# RAA214023GNP_HCA.net
KiCad netlist of a schematic drawn in Altium Designer
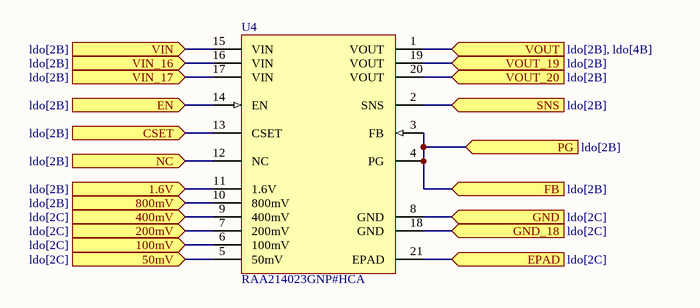
[diagram p0: RAA214023GNP#HCA.SchDoc]

(export (version "E")
  (design (tool "Eeschema 10.0.6"))
  (components
    (comp (ref "U4")
      (value "RAA214023GNP#HCA")
      (footprint "L20_3_5x3_5_MFG")
      (description "LDO Voltage Regulators 2A Low Noise LDO, 20 Lead 3.5x3.5 QFN (NiPdAu-Ag lead finish")
      (libsource (lib "Altium Content Vault") (part "bad0c6e7bfbbda4230ff4fb28f5c8c7"))
    )
  )
  (nets
    (net (code "1") (name "/1.6V") (class "Default")
      (node (ref "U4") (pin "11") (pinfunction "1.6V_11") (pintype "power_in"))
    )
    (net (code "2") (name "/50mV") (class "Default")
      (node (ref "U4") (pin "5") (pinfunction "50mV_5") (pintype "power_in"))
    )
    (net (code "3") (name "/100mV") (class "Default")
      (node (ref "U4") (pin "6") (pinfunction "100mV_6") (pintype "power_in"))
    )
    (net (code "4") (name "/200mV") (class "Default")
      (node (ref "U4") (pin "7") (pinfunction "200mV_7") (pintype "power_in"))
    )
    (net (code "5") (name "/400mV") (class "Default")
      (node (ref "U4") (pin "9") (pinfunction "400mV_9") (pintype "power_in"))
    )
    (net (code "6") (name "/800mV") (class "Default")
      (node (ref "U4") (pin "10") (pinfunction "800mV_10") (pintype "power_in"))
    )
    (net (code "7") (name "/CSET") (class "Default")
      (node (ref "U4") (pin "13") (pinfunction "CSET_13") (pintype "passive"))
    )
    (net (code "8") (name "/EN") (class "Default")
      (node (ref "U4") (pin "14") (pinfunction "EN_14") (pintype "input"))
    )
    (net (code "9") (name "/EPAD") (class "Default")
      (node (ref "U4") (pin "21") (pinfunction "EPAD_21") (pintype "power_in"))
    )
    (net (code "10") (name "/FB") (class "Default")
      (node (ref "U4") (pin "3") (pinfunction "FB_3") (pintype "input"))
      (node (ref "U4") (pin "4") (pinfunction "PG_4") (pintype "open_collector"))
    )
    (net (code "11") (name "/GND") (class "Default")
      (node (ref "U4") (pin "8") (pinfunction "GND_8") (pintype "power_in"))
    )
    (net (code "12") (name "/GND_18") (class "Default")
      (node (ref "U4") (pin "18") (pinfunction "GND_18") (pintype "power_in"))
    )
    (net (code "13") (name "/NC") (class "Default")
      (node (ref "U4") (pin "12") (pinfunction "NC_12") (pintype "passive"))
    )
    (net (code "14") (name "/SNS") (class "Default")
      (node (ref "U4") (pin "2") (pinfunction "SNS_2") (pintype "passive"))
    )
    (net (code "15") (name "/VIN") (class "Default")
      (node (ref "U4") (pin "15") (pinfunction "VIN_15") (pintype "power_in"))
    )
    (net (code "16") (name "/VIN_16") (class "Default")
      (node (ref "U4") (pin "16") (pinfunction "VIN_16") (pintype "power_in"))
    )
    (net (code "17") (name "/VIN_17") (class "Default")
      (node (ref "U4") (pin "17") (pinfunction "VIN_17") (pintype "power_in"))
    )
    (net (code "18") (name "/VOUT") (class "Default")
      (node (ref "U4") (pin "1") (pinfunction "VOUT_1") (pintype "power_in"))
    )
    (net (code "19") (name "/VOUT_19") (class "Default")
      (node (ref "U4") (pin "19") (pinfunction "VOUT_19") (pintype "power_in"))
    )
    (net (code "20") (name "/VOUT_20") (class "Default")
      (node (ref "U4") (pin "20") (pinfunction "VOUT_20") (pintype "power_in"))
    )
  )
)
